# MAX17502.net
KiCad netlist of a schematic drawn in Altium Designer
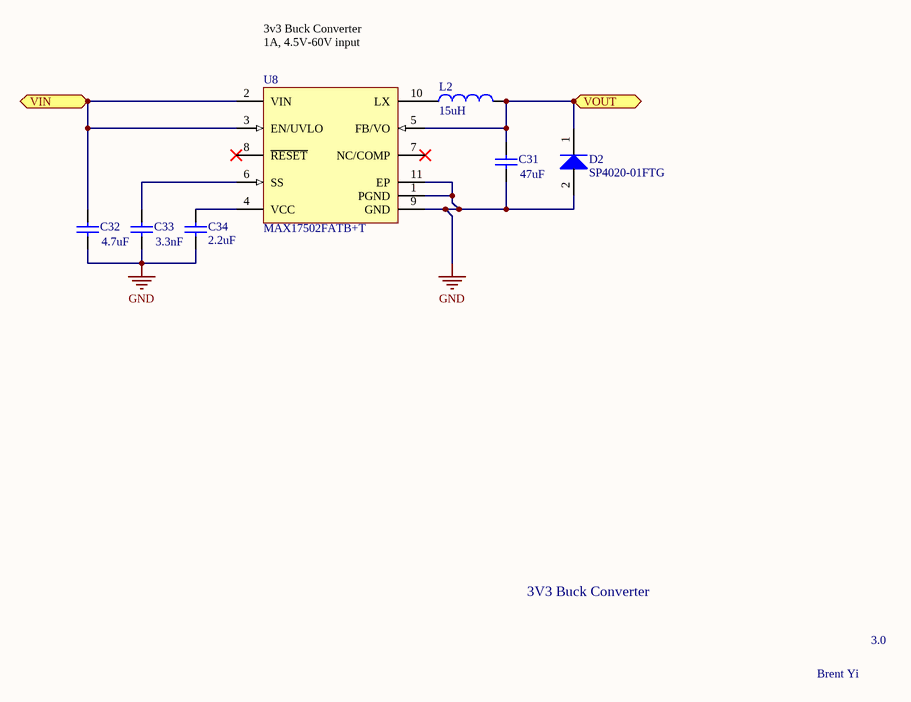
[diagram p0: MAX17502.SchDoc]

(export (version "E")
  (design (tool "Eeschema 10.0.6"))
  (components
    (comp (ref "C31")
      (value "47uF")
      (footprint "CAPC1210(3225)280_L")
      (description "CAP 100uF 10V Â±10% 1210 (3225 Metric) Thickness 2.8mm SMD")
      (fields (field (name "TOLERANCE") "Â±10%"))
      (libsource (lib "Altium Content Vault") (part "CMP-1038-02301-1"))
    )
    (comp (ref "C32")
      (value "4.7uF")
      (footprint "CAPC1210(3225)280_L")
      (description "CAP 100uF 10V Â±10% 1210 (3225 Metric) Thickness 2.8mm SMD")
      (fields (field (name "TOLERANCE") "Â±10%"))
      (libsource (lib "Altium Content Vault") (part "CMP-1038-02301-1"))
    )
    (comp (ref "C33")
      (value "3.3nF")
      (footprint "CAPC0603(1608)55_L")
      (description "CAP 2.2uF 16V Â±10% 0603 (1608 Metric) Thickness 0.55mm SMD")
      (fields (field (name "TOLERANCE") "Â±10%"))
      (libsource (lib "Altium Content Vault") (part "CMP-1035-02762-1"))
    )
    (comp (ref "C34")
      (value "2.2uF")
      (footprint "CAPC0603(1608)100_L")
      (description "CAP 1uF 6.3V Â±10% 0603 (1608 Metric) Thickness 1mm SMD")
      (fields (field (name "TOLERANCE") "Â±10%"))
      (libsource (lib "Altium Content Vault") (part "CMP-1035-02730-1"))
    )
    (comp (ref "D2")
      (value "SP4020-01FTG")
      (footprint "SOD323")
      (fields (field (name "PARTNUMBER") "MMSZ5262BT1G") (field (name "MANUFACTURER") "On Semiconductor"))
      (libsource (lib "Components") (part "SP4020-01FTG"))
    )
    (comp (ref "L2")
      (value "15uH")
      (footprint "SDR0604")
      (description "Inductor")
      (fields (field (name "Comment") "SDR0805-180ML") (field (name "PUBLISHER") "Altium Limited"))
      (libsource (lib "Components") (part "SDR0805-180ML"))
    )
    (comp (ref "U8")
      (value "MAX17502FATB+T")
      (footprint "MAXM-T1032N+1_V")
      (fields (field (name "MANUFACTURER") "Maxim"))
      (libsource (lib "Altium Content Vault") (part "MAXM-MAX17502-10"))
    )
  )
  (nets
    (net (code "1") (name "/VIN") (class "Default")
      (node (ref "C32") (pin "2") (pinfunction "2_2") (pintype "passive"))
      (node (ref "U8") (pin "2") (pinfunction "VIN_2") (pintype "power_in"))
      (node (ref "U8") (pin "3") (pinfunction "EN/UVLO_3") (pintype "input"))
    )
    (net (code "2") (name "/VOUT") (class "Default")
      (node (ref "C31") (pin "2") (pinfunction "2_2") (pintype "passive"))
      (node (ref "D2") (pin "1") (pinfunction "K_1") (pintype "passive"))
      (node (ref "L2") (pin "2") (pinfunction "2_2") (pintype "passive"))
      (node (ref "U8") (pin "5") (pinfunction "FB/VO_5") (pintype "input"))
    )
    (net (code "3") (name "GND") (class "Default")
      (node (ref "C31") (pin "1") (pinfunction "1_1") (pintype "passive"))
      (node (ref "C32") (pin "1") (pinfunction "1_1") (pintype "passive"))
      (node (ref "C33") (pin "2") (pinfunction "2_2") (pintype "passive"))
      (node (ref "C34") (pin "2") (pinfunction "2_2") (pintype "passive"))
      (node (ref "D2") (pin "2") (pinfunction "A_2") (pintype "passive"))
      (node (ref "U8") (pin "1") (pinfunction "PGND_1") (pintype "power_in"))
      (node (ref "U8") (pin "11") (pinfunction "EP_11") (pintype "power_in"))
      (node (ref "U8") (pin "9") (pinfunction "GND_9") (pintype "power_in"))
    )
    (net (code "4") (name "Net-(U8-LX)") (class "Default")
      (node (ref "L2") (pin "1") (pinfunction "1_1") (pintype "passive"))
      (node (ref "U8") (pin "10") (pinfunction "LX_10") (pintype "passive"))
    )
    (net (code "5") (name "Net-(U8-SS)") (class "Default")
      (node (ref "C33") (pin "1") (pinfunction "1_1") (pintype "passive"))
      (node (ref "U8") (pin "6") (pinfunction "SS_6") (pintype "input"))
    )
    (net (code "6") (name "Net-(U8-VCC)") (class "Default")
      (node (ref "C34") (pin "1") (pinfunction "1_1") (pintype "passive"))
      (node (ref "U8") (pin "4") (pinfunction "VCC_4") (pintype "power_in"))
    )
    (net (code "7") (name "unconnected-(U8-NC{slash}COMP-Pad7)") (class "Default")
      (node (ref "U8") (pin "7") (pinfunction "NC/COMP_7") (pintype "passive+no_connect"))
    )
    (net (code "8") (name "unconnected-(U8-~{RESET}-Pad8)") (class "Default")
      (node (ref "U8") (pin "8") (pinfunction "~{RESET}_8") (pintype "open_collector+no_connect"))
    )
  )
)
